# 17-Led.net
KiCad netlist of a schematic drawn in Altium Designer
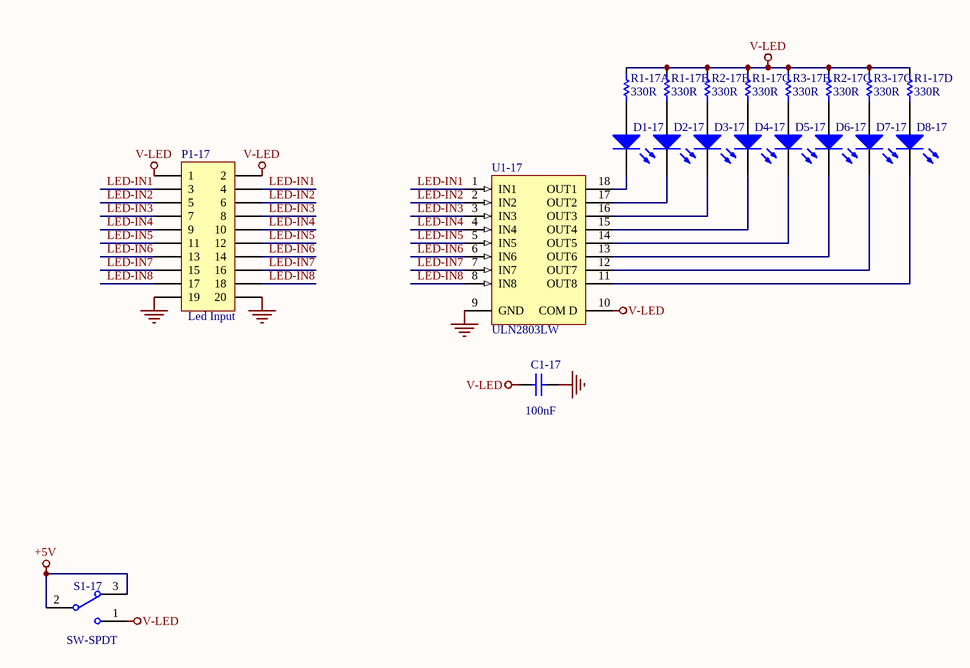
[diagram p0: 17-Led.SchDoc]

(export (version "E")
  (design (tool "Eeschema 10.0.6"))
  (components
    (comp (ref "C1-17")
      (value "100nF")
      (footprint "c-0805")
      (description "Capacitor")
      (fields (field (name "Comment") "104") (field (name "PUBLISHER") "Altium Limited"))
      (libsource (lib "Miscellaneous Devices") (part "Cap"))
    )
    (comp (ref "D1-17")
      (value "LED")
      (footprint "LED-0805")
      (description "Typical RED, GREEN, YELLOW, AMBER GaAs LED")
      (fields (field (name "PUBLISHER") "Altium Limited"))
      (libsource (lib "Miscellaneous Devices") (part "LED2"))
    )
    (comp (ref "D2-17")
      (value "LED")
      (footprint "LED-0805")
      (description "Typical RED, GREEN, YELLOW, AMBER GaAs LED")
      (fields (field (name "PUBLISHER") "Altium Limited"))
      (libsource (lib "Miscellaneous Devices") (part "LED2"))
    )
    (comp (ref "D3-17")
      (value "LED")
      (footprint "LED-0805")
      (description "Typical RED, GREEN, YELLOW, AMBER GaAs LED")
      (fields (field (name "PUBLISHER") "Altium Limited"))
      (libsource (lib "Miscellaneous Devices") (part "LED2"))
    )
    (comp (ref "D4-17")
      (value "LED")
      (footprint "LED-0805")
      (description "Typical RED, GREEN, YELLOW, AMBER GaAs LED")
      (fields (field (name "PUBLISHER") "Altium Limited"))
      (libsource (lib "Miscellaneous Devices") (part "LED2"))
    )
    (comp (ref "D5-17")
      (value "LED")
      (footprint "LED-0805")
      (description "Typical RED, GREEN, YELLOW, AMBER GaAs LED")
      (fields (field (name "PUBLISHER") "Altium Limited"))
      (libsource (lib "Miscellaneous Devices") (part "LED2"))
    )
    (comp (ref "D6-17")
      (value "LED")
      (footprint "LED-0805")
      (description "Typical RED, GREEN, YELLOW, AMBER GaAs LED")
      (fields (field (name "PUBLISHER") "Altium Limited"))
      (libsource (lib "Miscellaneous Devices") (part "LED2"))
    )
    (comp (ref "D7-17")
      (value "LED")
      (footprint "LED-0805")
      (description "Typical RED, GREEN, YELLOW, AMBER GaAs LED")
      (fields (field (name "PUBLISHER") "Altium Limited"))
      (libsource (lib "Miscellaneous Devices") (part "LED2"))
    )
    (comp (ref "D8-17")
      (value "LED")
      (footprint "LED-0805")
      (description "Typical RED, GREEN, YELLOW, AMBER GaAs LED")
      (fields (field (name "PUBLISHER") "Altium Limited"))
      (libsource (lib "Miscellaneous Devices") (part "LED2"))
    )
    (comp (ref "P1-17")
      (value "Led Input")
      (footprint "JP2.54-F-2x10A")
      (description "Header, 10-Pin, Dual row")
      (fields (field (name "Comment") "H10X2"))
      (libsource (lib "Miscellaneous Connectors") (part "Header 10X2"))
    )
    (comp (ref "R1-17")
      (value "330R")
      (footprint "R-Array-0603-4")
      (description "RES ARRAY 4 RES 330 OHM 1206")
      (fields
        (field (name "DIGI-KEY PART NUMBER") "Y9331TR-ND")
        (field (name "MANUFACTURER") "Panasonic Electronic Components")
      )
      (libsource (lib "Dlib") (part "R-8P4R"))
    )
    (comp (ref "R2-17")
      (value "330R")
      (footprint "R-Array-0603-4")
      (description "RES ARRAY 4 RES 330 OHM 1206")
      (fields
        (field (name "DIGI-KEY PART NUMBER") "Y9331TR-ND")
        (field (name "MANUFACTURER") "Panasonic Electronic Components")
      )
      (libsource (lib "Dlib") (part "R-8P4R"))
    )
    (comp (ref "R3-17")
      (value "330R")
      (footprint "R-Array-0603-4")
      (description "RES ARRAY 4 RES 330 OHM 1206")
      (fields
        (field (name "DIGI-KEY PART NUMBER") "Y9331TR-ND")
        (field (name "MANUFACTURER") "Panasonic Electronic Components")
      )
      (libsource (lib "Dlib") (part "R-8P4R"))
    )
    (comp (ref "S1-17")
      (value "SW-SPDT")
      (footprint "SW-SLIDE-2P-2W")
      (description "SPDT Subminiature Toggle Switch, Right Angle Mounting, Vertical Actuation")
      (fields (field (name "PUBLISHER") "Altium Limited"))
      (libsource (lib "Miscellaneous Devices") (part "SW-SPDT"))
    )
    (comp (ref "U1-17")
      (value "ULN2803LW")
      (footprint "SOIC-18-W")
      (description "High-Voltage, High-Current Darlington Array")
      (fields (field (name "PUBLISHER") "Altium Limited"))
      (libsource (lib "Allegro Interface Darlington Driver") (part "ULN2803LW"))
    )
  )
  (nets
    (net (code "1") (name "+5V") (class "Default")
      (node (ref "S1-17") (pin "2") (pinfunction "2_2") (pintype "passive"))
      (node (ref "S1-17") (pin "3") (pinfunction "3_3") (pintype "passive"))
    )
    (net (code "2") (name "/LED-IN1") (class "Default")
      (node (ref "P1-17") (pin "3") (pinfunction "3_3") (pintype "passive"))
      (node (ref "P1-17") (pin "4") (pinfunction "4_4") (pintype "passive"))
      (node (ref "U1-17") (pin "1") (pinfunction "IN1_1") (pintype "input"))
    )
    (net (code "3") (name "/LED-IN2") (class "Default")
      (node (ref "P1-17") (pin "5") (pinfunction "5_5") (pintype "passive"))
      (node (ref "P1-17") (pin "6") (pinfunction "6_6") (pintype "passive"))
      (node (ref "U1-17") (pin "2") (pinfunction "IN2_2") (pintype "input"))
    )
    (net (code "4") (name "/LED-IN3") (class "Default")
      (node (ref "P1-17") (pin "7") (pinfunction "7_7") (pintype "passive"))
      (node (ref "P1-17") (pin "8") (pinfunction "8_8") (pintype "passive"))
      (node (ref "U1-17") (pin "3") (pinfunction "IN3_3") (pintype "input"))
    )
    (net (code "5") (name "/LED-IN4") (class "Default")
      (node (ref "P1-17") (pin "10") (pinfunction "10_10") (pintype "passive"))
      (node (ref "P1-17") (pin "9") (pinfunction "9_9") (pintype "passive"))
      (node (ref "U1-17") (pin "4") (pinfunction "IN4_4") (pintype "input"))
    )
    (net (code "6") (name "/LED-IN5") (class "Default")
      (node (ref "P1-17") (pin "11") (pinfunction "11_11") (pintype "passive"))
      (node (ref "P1-17") (pin "12") (pinfunction "12_12") (pintype "passive"))
      (node (ref "U1-17") (pin "5") (pinfunction "IN5_5") (pintype "input"))
    )
    (net (code "7") (name "/LED-IN6") (class "Default")
      (node (ref "P1-17") (pin "13") (pinfunction "13_13") (pintype "passive"))
      (node (ref "P1-17") (pin "14") (pinfunction "14_14") (pintype "passive"))
      (node (ref "U1-17") (pin "6") (pinfunction "IN6_6") (pintype "input"))
    )
    (net (code "8") (name "/LED-IN7") (class "Default")
      (node (ref "P1-17") (pin "15") (pinfunction "15_15") (pintype "passive"))
      (node (ref "P1-17") (pin "16") (pinfunction "16_16") (pintype "passive"))
      (node (ref "U1-17") (pin "7") (pinfunction "IN7_7") (pintype "input"))
    )
    (net (code "9") (name "/LED-IN8") (class "Default")
      (node (ref "P1-17") (pin "17") (pinfunction "17_17") (pintype "passive"))
      (node (ref "P1-17") (pin "18") (pinfunction "18_18") (pintype "passive"))
      (node (ref "U1-17") (pin "8") (pinfunction "IN8_8") (pintype "input"))
    )
    (net (code "10") (name "GND") (class "Default")
      (node (ref "C1-17") (pin "2") (pinfunction "2_2") (pintype "passive"))
      (node (ref "P1-17") (pin "19") (pinfunction "19_19") (pintype "passive"))
      (node (ref "P1-17") (pin "20") (pinfunction "20_20") (pintype "passive"))
      (node (ref "U1-17") (pin "9") (pinfunction "GND_9") (pintype "power_in"))
    )
    (net (code "11") (name "Net-(D1-17-A)") (class "Default")
      (node (ref "D1-17") (pin "1") (pinfunction "A_1") (pintype "passive"))
      (node (ref "R1-17") (pin "1") (pinfunction "1_1") (pintype "passive"))
    )
    (net (code "12") (name "Net-(D1-17-K)") (class "Default")
      (node (ref "D1-17") (pin "2") (pinfunction "K_2") (pintype "passive"))
      (node (ref "U1-17") (pin "18") (pinfunction "OUT1_18") (pintype "open_collector"))
    )
    (net (code "13") (name "Net-(D2-17-A)") (class "Default")
      (node (ref "D2-17") (pin "1") (pinfunction "A_1") (pintype "passive"))
      (node (ref "R1-17") (pin "3") (pinfunction "1_3") (pintype "passive"))
    )
    (net (code "14") (name "Net-(D2-17-K)") (class "Default")
      (node (ref "D2-17") (pin "2") (pinfunction "K_2") (pintype "passive"))
      (node (ref "U1-17") (pin "17") (pinfunction "OUT2_17") (pintype "open_collector"))
    )
    (net (code "15") (name "Net-(D3-17-A)") (class "Default")
      (node (ref "D3-17") (pin "1") (pinfunction "A_1") (pintype "passive"))
      (node (ref "R2-17") (pin "3") (pinfunction "1_3") (pintype "passive"))
    )
    (net (code "16") (name "Net-(D3-17-K)") (class "Default")
      (node (ref "D3-17") (pin "2") (pinfunction "K_2") (pintype "passive"))
      (node (ref "U1-17") (pin "16") (pinfunction "OUT3_16") (pintype "open_collector"))
    )
    (net (code "17") (name "Net-(D4-17-A)") (class "Default")
      (node (ref "D4-17") (pin "1") (pinfunction "A_1") (pintype "passive"))
      (node (ref "R1-17") (pin "5") (pinfunction "1_5") (pintype "passive"))
    )
    (net (code "18") (name "Net-(D4-17-K)") (class "Default")
      (node (ref "D4-17") (pin "2") (pinfunction "K_2") (pintype "passive"))
      (node (ref "U1-17") (pin "15") (pinfunction "OUT4_15") (pintype "open_collector"))
    )
    (net (code "19") (name "Net-(D5-17-A)") (class "Default")
      (node (ref "D5-17") (pin "1") (pinfunction "A_1") (pintype "passive"))
      (node (ref "R3-17") (pin "3") (pinfunction "1_3") (pintype "passive"))
    )
    (net (code "20") (name "Net-(D5-17-K)") (class "Default")
      (node (ref "D5-17") (pin "2") (pinfunction "K_2") (pintype "passive"))
      (node (ref "U1-17") (pin "14") (pinfunction "OUT5_14") (pintype "open_collector"))
    )
    (net (code "21") (name "Net-(D6-17-A)") (class "Default")
      (node (ref "D6-17") (pin "1") (pinfunction "A_1") (pintype "passive"))
      (node (ref "R2-17") (pin "5") (pinfunction "1_5") (pintype "passive"))
    )
    (net (code "22") (name "Net-(D6-17-K)") (class "Default")
      (node (ref "D6-17") (pin "2") (pinfunction "K_2") (pintype "passive"))
      (node (ref "U1-17") (pin "13") (pinfunction "OUT6_13") (pintype "open_collector"))
    )
    (net (code "23") (name "Net-(D7-17-A)") (class "Default")
      (node (ref "D7-17") (pin "1") (pinfunction "A_1") (pintype "passive"))
      (node (ref "R3-17") (pin "5") (pinfunction "1_5") (pintype "passive"))
    )
    (net (code "24") (name "Net-(D7-17-K)") (class "Default")
      (node (ref "D7-17") (pin "2") (pinfunction "K_2") (pintype "passive"))
      (node (ref "U1-17") (pin "12") (pinfunction "OUT7_12") (pintype "open_collector"))
    )
    (net (code "25") (name "Net-(D8-17-A)") (class "Default")
      (node (ref "D8-17") (pin "1") (pinfunction "A_1") (pintype "passive"))
      (node (ref "R1-17") (pin "7") (pinfunction "1_7") (pintype "passive"))
    )
    (net (code "26") (name "Net-(D8-17-K)") (class "Default")
      (node (ref "D8-17") (pin "2") (pinfunction "K_2") (pintype "passive"))
      (node (ref "U1-17") (pin "11") (pinfunction "OUT8_11") (pintype "open_collector"))
    )
    (net (code "27") (name "V-LED") (class "Default")
      (node (ref "C1-17") (pin "1") (pinfunction "1_1") (pintype "passive"))
      (node (ref "P1-17") (pin "1") (pinfunction "1_1") (pintype "passive"))
      (node (ref "P1-17") (pin "2") (pinfunction "2_2") (pintype "passive"))
      (node (ref "R1-17") (pin "2") (pinfunction "2_2") (pintype "passive"))
      (node (ref "R1-17") (pin "4") (pinfunction "2_4") (pintype "passive"))
      (node (ref "R1-17") (pin "6") (pinfunction "2_6") (pintype "passive"))
      (node (ref "R1-17") (pin "8") (pinfunction "2_8") (pintype "passive"))
      (node (ref "R2-17") (pin "4") (pinfunction "2_4") (pintype "passive"))
      (node (ref "R2-17") (pin "6") (pinfunction "2_6") (pintype "passive"))
      (node (ref "R3-17") (pin "4") (pinfunction "2_4") (pintype "passive"))
      (node (ref "R3-17") (pin "6") (pinfunction "2_6") (pintype "passive"))
      (node (ref "S1-17") (pin "1") (pinfunction "1_1") (pintype "passive"))
      (node (ref "U1-17") (pin "10") (pinfunction "COM_D_10") (pintype "passive"))
    )
  )
)
